# X2C_DC_SHIELD_REVA.net
KiCad netlist of a schematic drawn in EAGLE
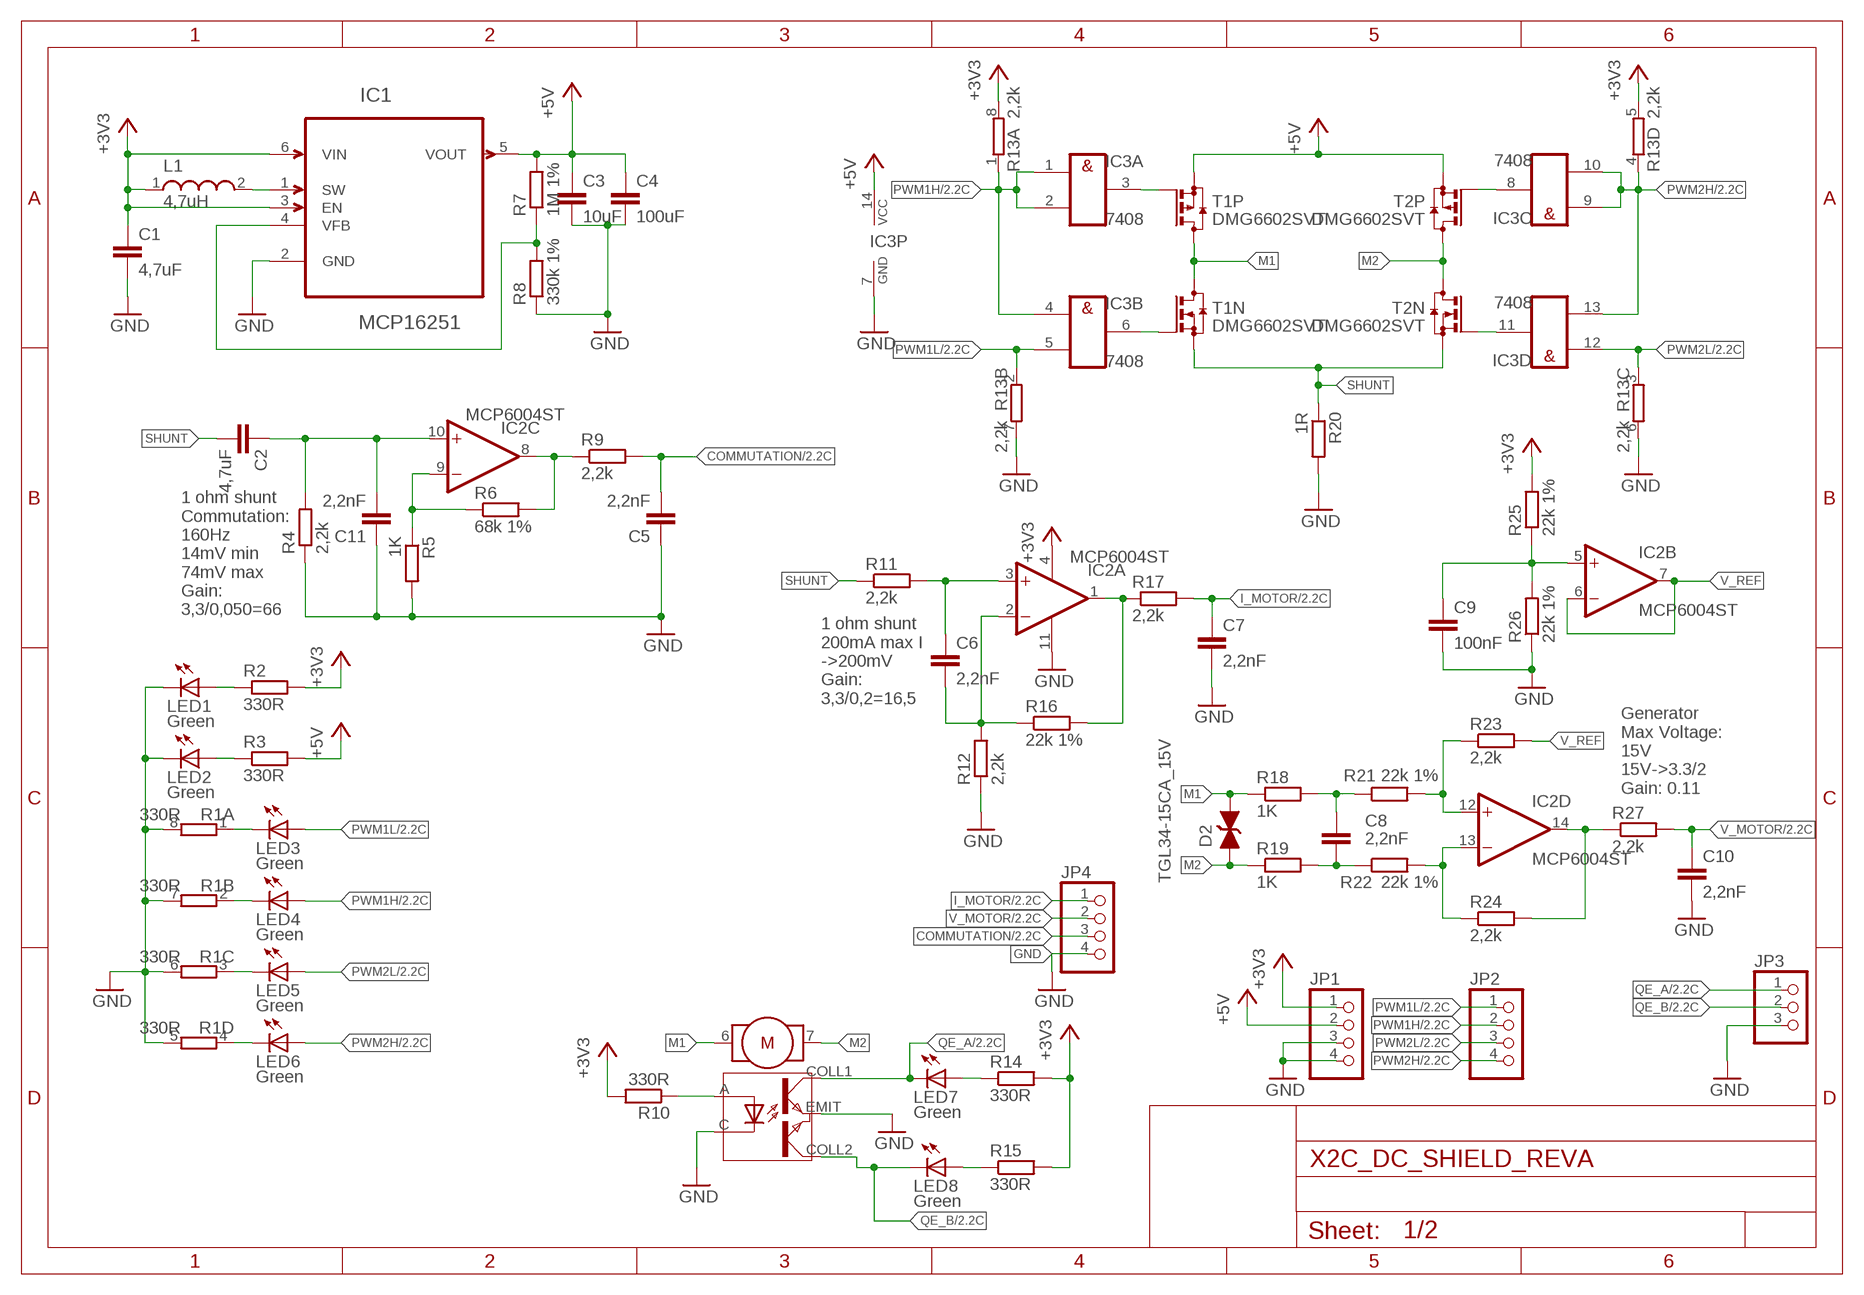
[diagram p0: schematic, sheet 1]
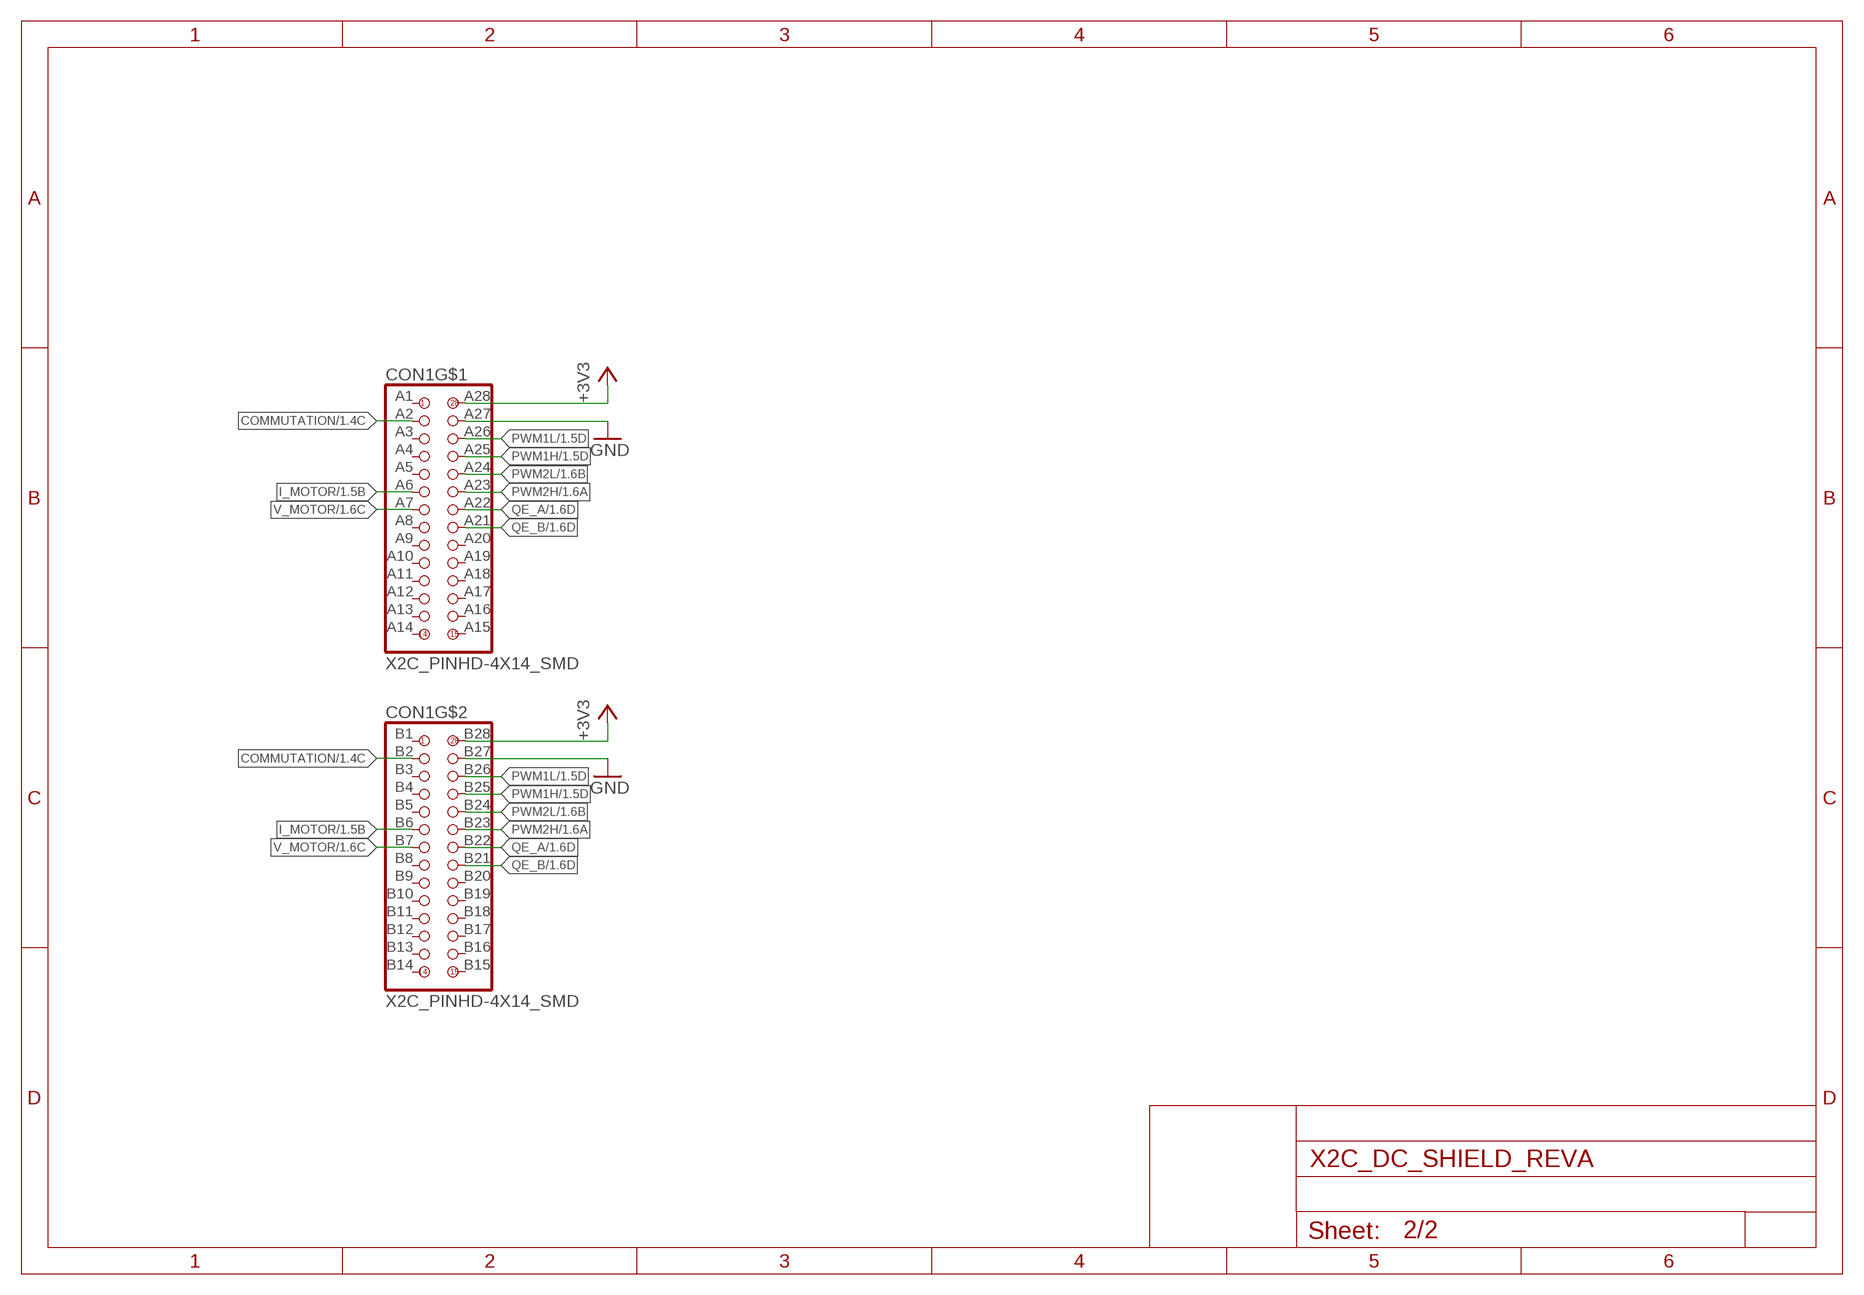
[diagram p1: schematic, sheet 2]

(export (version "E")
  (design (tool "Eeschema 10.0.6"))
  (components
    (comp (ref "C1")
      (value "4,7uF")
      (footprint "eagle-import:C0603K")
      (libsource (lib "eagle-import") (part "C-EU-SMD_0603_4,7UF_16V"))
    )
    (comp (ref "C2")
      (value "4,7uF")
      (footprint "eagle-import:C0603K")
      (libsource (lib "eagle-import") (part "C-EU-SMD_0603_4,7UF_16V"))
    )
    (comp (ref "C3")
      (value "10uF")
      (footprint "eagle-import:C0805K")
      (libsource (lib "eagle-import") (part "C-EU-SMD_0805_10UF_16V"))
    )
    (comp (ref "C4")
      (value "100uF")
      (footprint "eagle-import:C0805K")
      (libsource (lib "eagle-import") (part "C-EU-SMD_0805_100UF_6,3V"))
    )
    (comp (ref "C5")
      (value "2,2nF")
      (footprint "eagle-import:C0603K")
      (libsource (lib "eagle-import") (part "C-EU-SMD_0603_2,2NF"))
    )
    (comp (ref "C6")
      (value "2,2nF")
      (footprint "eagle-import:C0603K")
      (libsource (lib "eagle-import") (part "C-EU-SMD_0603_2,2NF"))
    )
    (comp (ref "C7")
      (value "2,2nF")
      (footprint "eagle-import:C0603K")
      (libsource (lib "eagle-import") (part "C-EU-SMD_0603_2,2NF"))
    )
    (comp (ref "C8")
      (value "2,2nF")
      (footprint "eagle-import:C0603K")
      (libsource (lib "eagle-import") (part "C-EU-SMD_0603_2,2NF"))
    )
    (comp (ref "C9")
      (value "100nF")
      (footprint "eagle-import:C0603K")
      (libsource (lib "eagle-import") (part "C-EU-SMD_0603_100NF_50V"))
    )
    (comp (ref "C10")
      (value "2,2nF")
      (footprint "eagle-import:C0603K")
      (libsource (lib "eagle-import") (part "C-EU-SMD_0603_2,2NF"))
    )
    (comp (ref "C11")
      (value "2,2nF")
      (footprint "eagle-import:C0603K")
      (libsource (lib "eagle-import") (part "C-EU-SMD_0603_2,2NF"))
    )
    (comp (ref "D2")
      (value "TGL34-15CA_15V")
      (footprint "eagle-import:DO213AA")
      (libsource (lib "eagle-import") (part "TRANSIL_DUAL_DIODE"))
    )
    (comp (ref "IC1")
      (value "MCP16251")
      (footprint "eagle-import:SOT95P270X145-6N")
      (libsource (lib "eagle-import") (part "MCP16251"))
    )
    (comp (ref "IC2")
      (value "MCP6004ST")
      (footprint "eagle-import:TSSOP14")
      (libsource (lib "eagle-import") (part "MCP6004ST"))
    )
    (comp (ref "IC3")
      (value "7408")
      (footprint "eagle-import:TSSOP14")
      (libsource (lib "eagle-import") (part "7408"))
    )
    (comp (ref "JP1")
      (value "PINHD-1X4")
      (footprint "eagle-import:1X04")
      (libsource (lib "eagle-import") (part "PINHD-1X4"))
    )
    (comp (ref "JP2")
      (value "PINHD-1X4")
      (footprint "eagle-import:1X04")
      (libsource (lib "eagle-import") (part "PINHD-1X4"))
    )
    (comp (ref "JP3")
      (value "PINHD-1X03_2.54")
      (footprint "eagle-import:1X03")
      (libsource (lib "eagle-import") (part "PINHD-1X03_2.54"))
    )
    (comp (ref "JP4")
      (value "PINHD-1X4")
      (footprint "eagle-import:1X04")
      (libsource (lib "eagle-import") (part "PINHD-1X4"))
    )
    (comp (ref "L1")
      (value "4,7uH")
      (footprint "eagle-import:WE-TPC_3816")
      (libsource (lib "eagle-import") (part "WE-TPC_3816_4,7UH_0,9A"))
    )
    (comp (ref "LED1")
      (value "Green")
      (footprint "eagle-import:CHIPLED_0805")
      (libsource (lib "eagle-import") (part "LEDCHIPLED_0805_GREEN"))
    )
    (comp (ref "LED2")
      (value "Green")
      (footprint "eagle-import:CHIPLED_0805")
      (libsource (lib "eagle-import") (part "LEDCHIPLED_0805_GREEN"))
    )
    (comp (ref "LED3")
      (value "Green")
      (footprint "eagle-import:CHIPLED_0805")
      (libsource (lib "eagle-import") (part "LEDCHIPLED_0805_GREEN"))
    )
    (comp (ref "LED4")
      (value "Green")
      (footprint "eagle-import:CHIPLED_0805")
      (libsource (lib "eagle-import") (part "LEDCHIPLED_0805_GREEN"))
    )
    (comp (ref "LED5")
      (value "Green")
      (footprint "eagle-import:CHIPLED_0805")
      (libsource (lib "eagle-import") (part "LEDCHIPLED_0805_GREEN"))
    )
    (comp (ref "LED6")
      (value "Green")
      (footprint "eagle-import:CHIPLED_0805")
      (libsource (lib "eagle-import") (part "LEDCHIPLED_0805_GREEN"))
    )
    (comp (ref "LED7")
      (value "Green")
      (footprint "eagle-import:CHIPLED_0805")
      (libsource (lib "eagle-import") (part "LEDCHIPLED_0805_GREEN"))
    )
    (comp (ref "LED8")
      (value "Green")
      (footprint "eagle-import:CHIPLED_0805")
      (libsource (lib "eagle-import") (part "LEDCHIPLED_0805_GREEN"))
    )
    (comp (ref "MOT1")
      (value "DC_MOT")
      (footprint "eagle-import:DC_MOTOR")
      (libsource (lib "eagle-import") (part "DC_MOTOR_1"))
    )
    (comp (ref "R1")
      (value "330R")
      (footprint "eagle-import:EXBV8V_A")
      (libsource (lib "eagle-import") (part "4R-N330R"))
    )
    (comp (ref "R2")
      (value "330R")
      (footprint "eagle-import:R0603")
      (libsource (lib "eagle-import") (part "R-EU_SMDR0603_330R"))
    )
    (comp (ref "R3")
      (value "330R")
      (footprint "eagle-import:R0603")
      (libsource (lib "eagle-import") (part "R-EU_SMDR0603_330R"))
    )
    (comp (ref "R4")
      (value "2,2k")
      (footprint "eagle-import:R0603")
      (libsource (lib "eagle-import") (part "R-EU_SMDR0603_2,2K"))
    )
    (comp (ref "R5")
      (value "1K")
      (footprint "eagle-import:R0603")
      (libsource (lib "eagle-import") (part "R-EU_SMDR0603_1K_1%"))
    )
    (comp (ref "R6")
      (value "68k 1%")
      (footprint "eagle-import:R0603")
      (libsource (lib "eagle-import") (part "R-EU_SMDR0603_68K_1%"))
    )
    (comp (ref "R7")
      (value "1M 1%")
      (footprint "eagle-import:R0603")
      (libsource (lib "eagle-import") (part "R-EU_SMDR0603_1M_1%"))
    )
    (comp (ref "R8")
      (value "330k 1%")
      (footprint "eagle-import:R0603")
      (libsource (lib "eagle-import") (part "R-EU_SMDR0603_330K_1%"))
    )
    (comp (ref "R9")
      (value "2,2k")
      (footprint "eagle-import:R0603")
      (libsource (lib "eagle-import") (part "R-EU_SMDR0603_2,2K"))
    )
    (comp (ref "R10")
      (value "330R")
      (footprint "eagle-import:R0603")
      (libsource (lib "eagle-import") (part "R-EU_SMDR0603_330R"))
    )
    (comp (ref "R11")
      (value "2,2k")
      (footprint "eagle-import:R0603")
      (libsource (lib "eagle-import") (part "R-EU_SMDR0603_2,2K"))
    )
    (comp (ref "R12")
      (value "2,2k")
      (footprint "eagle-import:R0603")
      (libsource (lib "eagle-import") (part "R-EU_SMDR0603_2,2K"))
    )
    (comp (ref "R13")
      (value "2,2k")
      (footprint "eagle-import:EXBV8V_A")
      (libsource (lib "eagle-import") (part "4R-N2,2K"))
    )
    (comp (ref "R14")
      (value "330R")
      (footprint "eagle-import:R0603")
      (libsource (lib "eagle-import") (part "R-EU_SMDR0603_330R"))
    )
    (comp (ref "R15")
      (value "330R")
      (footprint "eagle-import:R0603")
      (libsource (lib "eagle-import") (part "R-EU_SMDR0603_330R"))
    )
    (comp (ref "R16")
      (value "22k 1%")
      (footprint "eagle-import:R0603")
      (libsource (lib "eagle-import") (part "R-EU_SMDR0603_22K_1%"))
    )
    (comp (ref "R17")
      (value "2,2k")
      (footprint "eagle-import:R0603")
      (libsource (lib "eagle-import") (part "R-EU_SMDR0603_2,2K"))
    )
    (comp (ref "R18")
      (value "1K")
      (footprint "eagle-import:R0603")
      (libsource (lib "eagle-import") (part "R-EU_SMDR0603_1K_1%"))
    )
    (comp (ref "R19")
      (value "1K")
      (footprint "eagle-import:R0603")
      (libsource (lib "eagle-import") (part "R-EU_SMDR0603_1K_1%"))
    )
    (comp (ref "R20")
      (value "1R")
      (footprint "eagle-import:R0805")
      (libsource (lib "eagle-import") (part "R-EU_SMDR0805_1R_1%"))
    )
    (comp (ref "R21")
      (value "22k 1%")
      (footprint "eagle-import:R0603")
      (libsource (lib "eagle-import") (part "R-EU_SMDR0603_22K_1%"))
    )
    (comp (ref "R22")
      (value "22k 1%")
      (footprint "eagle-import:R0603")
      (libsource (lib "eagle-import") (part "R-EU_SMDR0603_22K_1%"))
    )
    (comp (ref "R23")
      (value "2,2k")
      (footprint "eagle-import:R0603")
      (libsource (lib "eagle-import") (part "R-EU_SMDR0603_2,2K"))
    )
    (comp (ref "R24")
      (value "2,2k")
      (footprint "eagle-import:R0603")
      (libsource (lib "eagle-import") (part "R-EU_SMDR0603_2,2K"))
    )
    (comp (ref "R25")
      (value "22k 1%")
      (footprint "eagle-import:R0603")
      (libsource (lib "eagle-import") (part "R-EU_SMDR0603_22K_1%"))
    )
    (comp (ref "R26")
      (value "22k 1%")
      (footprint "eagle-import:R0603")
      (libsource (lib "eagle-import") (part "R-EU_SMDR0603_22K_1%"))
    )
    (comp (ref "R27")
      (value "2,2k")
      (footprint "eagle-import:R0603")
      (libsource (lib "eagle-import") (part "R-EU_SMDR0603_2,2K"))
    )
    (comp (ref "T1")
      (value "DMG6602SVT")
      (footprint "eagle-import:TSOT23-6")
      (libsource (lib "eagle-import") (part "DMG6602SVT"))
    )
    (comp (ref "T2")
      (value "DMG6602SVT")
      (footprint "eagle-import:TSOT23-6")
      (libsource (lib "eagle-import") (part "DMG6602SVT"))
    )
    (comp (ref "CON1")
      (value "X2C_PINHD-4X14_SMD")
      (footprint "eagle-import:X2C_4X14_SMD")
      (libsource (lib "eagle-import") (part "X2C_PINHD-4X14_SMD"))
    )
  )
  (nets
    (net (code "1") (name "+3V3") (class "Default")
      (node (ref "C1") (pin "1") (pinfunction "1_1") (pintype "passive"))
      (node (ref "CON1") (pin "A28") (pinfunction "A28_A28") (pintype "passive"))
      (node (ref "CON1") (pin "B28") (pinfunction "A28_B28") (pintype "passive"))
      (node (ref "IC1") (pin "3") (pinfunction "EN_3") (pintype "input"))
      (node (ref "IC1") (pin "6") (pinfunction "VIN_6") (pintype "input"))
      (node (ref "IC2") (pin "4") (pinfunction "V+_4") (pintype "power_in"))
      (node (ref "JP1") (pin "1") (pinfunction "1_1") (pintype "passive"))
      (node (ref "L1") (pin "1") (pinfunction "1_1") (pintype "passive"))
      (node (ref "R10") (pin "2") (pinfunction "2_2") (pintype "passive"))
      (node (ref "R13") (pin "5") (pinfunction "2_5") (pintype "passive"))
      (node (ref "R13") (pin "8") (pinfunction "2_8") (pintype "passive"))
      (node (ref "R14") (pin "2") (pinfunction "2_2") (pintype "passive"))
      (node (ref "R15") (pin "2") (pinfunction "2_2") (pintype "passive"))
      (node (ref "R2") (pin "2") (pinfunction "2_2") (pintype "passive"))
      (node (ref "R25") (pin "2") (pinfunction "2_2") (pintype "passive"))
    )
    (net (code "2") (name "+5V") (class "Default")
      (node (ref "C3") (pin "1") (pinfunction "1_1") (pintype "passive"))
      (node (ref "C4") (pin "1") (pinfunction "1_1") (pintype "passive"))
      (node (ref "IC1") (pin "5") (pinfunction "VOUT_5") (pintype "output"))
      (node (ref "IC3") (pin "14") (pinfunction "VCC_14") (pintype "power_in"))
      (node (ref "JP1") (pin "2") (pinfunction "2_2") (pintype "passive"))
      (node (ref "R3") (pin "2") (pinfunction "2_2") (pintype "passive"))
      (node (ref "R7") (pin "2") (pinfunction "2_2") (pintype "passive"))
      (node (ref "T1") (pin "2") (pinfunction "S_2") (pintype "passive"))
      (node (ref "T2") (pin "2") (pinfunction "S_2") (pintype "passive"))
    )
    (net (code "3") (name "COMMUTATION") (class "Default")
      (node (ref "C5") (pin "2") (pinfunction "2_2") (pintype "passive"))
      (node (ref "CON1") (pin "A2") (pinfunction "A2_A2") (pintype "passive"))
      (node (ref "CON1") (pin "B2") (pinfunction "A2_B2") (pintype "passive"))
      (node (ref "JP4") (pin "3") (pinfunction "3_3") (pintype "passive"))
      (node (ref "R9") (pin "2") (pinfunction "2_2") (pintype "passive"))
    )
    (net (code "4") (name "GND") (class "Default")
      (node (ref "C1") (pin "2") (pinfunction "2_2") (pintype "passive"))
      (node (ref "C10") (pin "2") (pinfunction "2_2") (pintype "passive"))
      (node (ref "C11") (pin "1") (pinfunction "1_1") (pintype "passive"))
      (node (ref "C3") (pin "2") (pinfunction "2_2") (pintype "passive"))
      (node (ref "C4") (pin "2") (pinfunction "2_2") (pintype "passive"))
      (node (ref "C5") (pin "1") (pinfunction "1_1") (pintype "passive"))
      (node (ref "C7") (pin "2") (pinfunction "2_2") (pintype "passive"))
      (node (ref "C9") (pin "2") (pinfunction "2_2") (pintype "passive"))
      (node (ref "CON1") (pin "A27") (pinfunction "A27_A27") (pintype "passive"))
      (node (ref "CON1") (pin "B27") (pinfunction "A27_B27") (pintype "passive"))
      (node (ref "IC1") (pin "2") (pinfunction "GND_2") (pintype "passive"))
      (node (ref "IC2") (pin "11") (pinfunction "V-_11") (pintype "power_in"))
      (node (ref "IC3") (pin "7") (pinfunction "GND_7") (pintype "power_in"))
      (node (ref "JP1") (pin "3") (pinfunction "3_3") (pintype "passive"))
      (node (ref "JP1") (pin "4") (pinfunction "4_4") (pintype "passive"))
      (node (ref "JP3") (pin "3") (pinfunction "3_3") (pintype "passive"))
      (node (ref "JP4") (pin "4") (pinfunction "4_4") (pintype "passive"))
      (node (ref "LED1") (pin "C") (pinfunction "C_C") (pintype "passive"))
      (node (ref "LED2") (pin "C") (pinfunction "C_C") (pintype "passive"))
      (node (ref "MOT1") (pin "C") (pinfunction "C_C") (pintype "passive"))
      (node (ref "MOT1") (pin "EMIT") (pinfunction "EMIT_EMIT") (pintype "passive"))
      (node (ref "R1") (pin "5") (pinfunction "2_5") (pintype "passive"))
      (node (ref "R1") (pin "6") (pinfunction "2_6") (pintype "passive"))
      (node (ref "R1") (pin "7") (pinfunction "2_7") (pintype "passive"))
      (node (ref "R1") (pin "8") (pinfunction "2_8") (pintype "passive"))
      (node (ref "R12") (pin "1") (pinfunction "1_1") (pintype "passive"))
      (node (ref "R13") (pin "6") (pinfunction "2_6") (pintype "passive"))
      (node (ref "R13") (pin "7") (pinfunction "2_7") (pintype "passive"))
      (node (ref "R20") (pin "2") (pinfunction "2_2") (pintype "passive"))
      (node (ref "R26") (pin "1") (pinfunction "1_1") (pintype "passive"))
      (node (ref "R4") (pin "1") (pinfunction "1_1") (pintype "passive"))
      (node (ref "R5") (pin "2") (pinfunction "2_2") (pintype "passive"))
      (node (ref "R8") (pin "1") (pinfunction "1_1") (pintype "passive"))
    )
    (net (code "5") (name "I_MOTOR") (class "Default")
      (node (ref "C7") (pin "1") (pinfunction "1_1") (pintype "passive"))
      (node (ref "CON1") (pin "A6") (pinfunction "A6_A6") (pintype "passive"))
      (node (ref "CON1") (pin "B6") (pinfunction "A6_B6") (pintype "passive"))
      (node (ref "JP4") (pin "1") (pinfunction "1_1") (pintype "passive"))
      (node (ref "R17") (pin "2") (pinfunction "2_2") (pintype "passive"))
    )
    (net (code "6") (name "M1") (class "Default")
      (node (ref "D2") (pin "C") (pinfunction "P$2_C") (pintype "bidirectional"))
      (node (ref "MOT1") (pin "6") (pinfunction "MOT1_6") (pintype "passive"))
      (node (ref "R18") (pin "1") (pinfunction "1_1") (pintype "passive"))
      (node (ref "T1") (pin "4") (pinfunction "D_4") (pintype "passive"))
      (node (ref "T1") (pin "6") (pinfunction "D_6") (pintype "passive"))
    )
    (net (code "7") (name "M2") (class "Default")
      (node (ref "D2") (pin "A") (pinfunction "P$1_A") (pintype "bidirectional"))
      (node (ref "MOT1") (pin "7") (pinfunction "MOT2_7") (pintype "passive"))
      (node (ref "R19") (pin "1") (pinfunction "1_1") (pintype "passive"))
      (node (ref "T2") (pin "4") (pinfunction "D_4") (pintype "passive"))
      (node (ref "T2") (pin "6") (pinfunction "D_6") (pintype "passive"))
    )
    (net (code "8") (name "Net-(C8-Pad1)") (class "Default")
      (node (ref "C8") (pin "1") (pinfunction "1_1") (pintype "passive"))
      (node (ref "R18") (pin "2") (pinfunction "2_2") (pintype "passive"))
      (node (ref "R21") (pin "1") (pinfunction "1_1") (pintype "passive"))
    )
    (net (code "9") (name "Net-(C8-Pad2)") (class "Default")
      (node (ref "C8") (pin "2") (pinfunction "2_2") (pintype "passive"))
      (node (ref "R19") (pin "2") (pinfunction "2_2") (pintype "passive"))
      (node (ref "R22") (pin "1") (pinfunction "1_1") (pintype "passive"))
    )
    (net (code "10") (name "Net-(IC1-SW)") (class "Default")
      (node (ref "IC1") (pin "1") (pinfunction "SW_1") (pintype "input"))
      (node (ref "L1") (pin "2") (pinfunction "2_2") (pintype "passive"))
    )
    (net (code "11") (name "Net-(IC1-VFB)") (class "Default")
      (node (ref "IC1") (pin "4") (pinfunction "VFB_4") (pintype "input"))
      (node (ref "R7") (pin "1") (pinfunction "1_1") (pintype "passive"))
      (node (ref "R8") (pin "2") (pinfunction "2_2") (pintype "passive"))
    )
    (net (code "12") (name "Net-(IC2A-+IN)") (class "Default")
      (node (ref "C6") (pin "1") (pinfunction "1_1") (pintype "passive"))
      (node (ref "IC2") (pin "3") (pinfunction "+IN_3") (pintype "input"))
      (node (ref "R11") (pin "2") (pinfunction "2_2") (pintype "passive"))
    )
    (net (code "13") (name "Net-(IC2A--IN)") (class "Default")
      (node (ref "C6") (pin "2") (pinfunction "2_2") (pintype "passive"))
      (node (ref "IC2") (pin "2") (pinfunction "-IN_2") (pintype "input"))
      (node (ref "R12") (pin "2") (pinfunction "2_2") (pintype "passive"))
      (node (ref "R16") (pin "1") (pinfunction "1_1") (pintype "passive"))
    )
    (net (code "14") (name "Net-(IC2A-OUT)") (class "Default")
      (node (ref "IC2") (pin "1") (pinfunction "OUT_1") (pintype "output"))
      (node (ref "R16") (pin "2") (pinfunction "2_2") (pintype "passive"))
      (node (ref "R17") (pin "1") (pinfunction "1_1") (pintype "passive"))
    )
    (net (code "15") (name "Net-(IC2B-+IN)") (class "Default")
      (node (ref "C9") (pin "1") (pinfunction "1_1") (pintype "passive"))
      (node (ref "IC2") (pin "5") (pinfunction "+IN_5") (pintype "input"))
      (node (ref "R25") (pin "1") (pinfunction "1_1") (pintype "passive"))
      (node (ref "R26") (pin "2") (pinfunction "2_2") (pintype "passive"))
    )
    (net (code "16") (name "Net-(IC2C-+IN)") (class "Default")
      (node (ref "C11") (pin "2") (pinfunction "2_2") (pintype "passive"))
      (node (ref "C2") (pin "1") (pinfunction "1_1") (pintype "passive"))
      (node (ref "IC2") (pin "10") (pinfunction "+IN_10") (pintype "input"))
      (node (ref "R4") (pin "2") (pinfunction "2_2") (pintype "passive"))
    )
    (net (code "17") (name "Net-(IC2C--IN)") (class "Default")
      (node (ref "IC2") (pin "9") (pinfunction "-IN_9") (pintype "input"))
      (node (ref "R5") (pin "1") (pinfunction "1_1") (pintype "passive"))
      (node (ref "R6") (pin "1") (pinfunction "1_1") (pintype "passive"))
    )
    (net (code "18") (name "Net-(IC2C-OUT)") (class "Default")
      (node (ref "IC2") (pin "8") (pinfunction "OUT_8") (pintype "output"))
      (node (ref "R6") (pin "2") (pinfunction "2_2") (pintype "passive"))
      (node (ref "R9") (pin "1") (pinfunction "1_1") (pintype "passive"))
    )
    (net (code "19") (name "Net-(IC2D-+IN)") (class "Default")
      (node (ref "IC2") (pin "12") (pinfunction "+IN_12") (pintype "input"))
      (node (ref "R21") (pin "2") (pinfunction "2_2") (pintype "passive"))
      (node (ref "R23") (pin "1") (pinfunction "1_1") (pintype "passive"))
    )
    (net (code "20") (name "Net-(IC2D--IN)") (class "Default")
      (node (ref "IC2") (pin "13") (pinfunction "-IN_13") (pintype "input"))
      (node (ref "R22") (pin "2") (pinfunction "2_2") (pintype "passive"))
      (node (ref "R24") (pin "1") (pinfunction "1_1") (pintype "passive"))
    )
    (net (code "21") (name "Net-(IC2D-OUT)") (class "Default")
      (node (ref "IC2") (pin "14") (pinfunction "OUT_14") (pintype "output"))
      (node (ref "R24") (pin "2") (pinfunction "2_2") (pintype "passive"))
      (node (ref "R27") (pin "1") (pinfunction "1_1") (pintype "passive"))
    )
    (net (code "22") (name "Net-(IC3A-O)") (class "Default")
      (node (ref "IC3") (pin "3") (pinfunction "O_3") (pintype "output"))
      (node (ref "T1") (pin "3") (pinfunction "G_3") (pintype "passive"))
    )
    (net (code "23") (name "Net-(IC3B-O)") (class "Default")
      (node (ref "IC3") (pin "6") (pinfunction "O_6") (pintype "output"))
      (node (ref "T1") (pin "1") (pinfunction "G_1") (pintype "passive"))
    )
    (net (code "24") (name "Net-(IC3C-O)") (class "Default")
      (node (ref "IC3") (pin "8") (pinfunction "O_8") (pintype "output"))
      (node (ref "T2") (pin "3") (pinfunction "G_3") (pintype "passive"))
    )
    (net (code "25") (name "Net-(IC3D-O)") (class "Default")
      (node (ref "IC3") (pin "11") (pinfunction "O_11") (pintype "output"))
      (node (ref "T2") (pin "1") (pinfunction "G_1") (pintype "passive"))
    )
    (net (code "26") (name "Net-(LED1-PadA)") (class "Default")
      (node (ref "LED1") (pin "A") (pinfunction "A_A") (pintype "passive"))
      (node (ref "R2") (pin "1") (pinfunction "1_1") (pintype "passive"))
    )
    (net (code "27") (name "Net-(LED2-PadA)") (class "Default")
      (node (ref "LED2") (pin "A") (pinfunction "A_A") (pintype "passive"))
      (node (ref "R3") (pin "1") (pinfunction "1_1") (pintype "passive"))
    )
    (net (code "28") (name "Net-(LED3-PadC)") (class "Default")
      (node (ref "LED3") (pin "C") (pinfunction "C_C") (pintype "passive"))
      (node (ref "R1") (pin "1") (pinfunction "1_1") (pintype "passive"))
    )
    (net (code "29") (name "Net-(LED7-PadA)") (class "Default")
      (node (ref "LED7") (pin "A") (pinfunction "A_A") (pintype "passive"))
      (node (ref "R14") (pin "1") (pinfunction "1_1") (pintype "passive"))
    )
    (net (code "30") (name "Net-(LED8-PadA)") (class "Default")
      (node (ref "LED8") (pin "A") (pinfunction "A_A") (pintype "passive"))
      (node (ref "R15") (pin "1") (pinfunction "1_1") (pintype "passive"))
    )
    (net (code "31") (name "Net-(MOT1-PadA)") (class "Default")
      (node (ref "MOT1") (pin "A") (pinfunction "A_A") (pintype "passive"))
      (node (ref "R10") (pin "1") (pinfunction "1_1") (pintype "passive"))
    )
    (net (code "32") (name "Net-(R1B-1)") (class "Default")
      (node (ref "LED4") (pin "C") (pinfunction "C_C") (pintype "passive"))
      (node (ref "R1") (pin "2") (pinfunction "1_2") (pintype "passive"))
    )
    (net (code "33") (name "Net-(R1C-1)") (class "Default")
      (node (ref "LED5") (pin "C") (pinfunction "C_C") (pintype "passive"))
      (node (ref "R1") (pin "3") (pinfunction "1_3") (pintype "passive"))
    )
    (net (code "34") (name "Net-(R1D-1)") (class "Default")
      (node (ref "LED6") (pin "C") (pinfunction "C_C") (pintype "passive"))
      (node (ref "R1") (pin "4") (pinfunction "1_4") (pintype "passive"))
    )
    (net (code "35") (name "PWM1H") (class "Default")
      (node (ref "CON1") (pin "A25") (pinfunction "A25_A25") (pintype "passive"))
      (node (ref "CON1") (pin "B25") (pinfunction "A25_B25") (pintype "passive"))
      (node (ref "IC3") (pin "1") (pinfunction "I0_1") (pintype "input"))
      (node (ref "IC3") (pin "2") (pinfunction "I1_2") (pintype "input"))
      (node (ref "IC3") (pin "4") (pinfunction "I0_4") (pintype "input"))
      (node (ref "JP2") (pin "2") (pinfunction "2_2") (pintype "passive"))
      (node (ref "LED4") (pin "A") (pinfunction "A_A") (pintype "passive"))
      (node (ref "R13") (pin "1") (pinfunction "1_1") (pintype "passive"))
    )
    (net (code "36") (name "PWM1L") (class "Default")
      (node (ref "CON1") (pin "A26") (pinfunction "A26_A26") (pintype "passive"))
      (node (ref "CON1") (pin "B26") (pinfunction "A26_B26") (pintype "passive"))
      (node (ref "IC3") (pin "5") (pinfunction "I1_5") (pintype "input"))
      (node (ref "JP2") (pin "1") (pinfunction "1_1") (pintype "passive"))
      (node (ref "LED3") (pin "A") (pinfunction "A_A") (pintype "passive"))
      (node (ref "R13") (pin "2") (pinfunction "1_2") (pintype "passive"))
    )
    (net (code "37") (name "PWM2H") (class "Default")
      (node (ref "CON1") (pin "A23") (pinfunction "A23_A23") (pintype "passive"))
      (node (ref "CON1") (pin "B23") (pinfunction "A23_B23") (pintype "passive"))
      (node (ref "IC3") (pin "10") (pinfunction "I1_10") (pintype "input"))
      (node (ref "IC3") (pin "13") (pinfunction "I1_13") (pintype "input"))
      (node (ref "IC3") (pin "9") (pinfunction "I0_9") (pintype "input"))
      (node (ref "JP2") (pin "4") (pinfunction "4_4") (pintype "passive"))
      (node (ref "LED6") (pin "A") (pinfunction "A_A") (pintype "passive"))
      (node (ref "R13") (pin "4") (pinfunction "1_4") (pintype "passive"))
    )
    (net (code "38") (name "PWM2L") (class "Default")
      (node (ref "CON1") (pin "A24") (pinfunction "A24_A24") (pintype "passive"))
      (node (ref "CON1") (pin "B24") (pinfunction "A24_B24") (pintype "passive"))
      (node (ref "IC3") (pin "12") (pinfunction "I0_12") (pintype "input"))
      (node (ref "JP2") (pin "3") (pinfunction "3_3") (pintype "passive"))
      (node (ref "LED5") (pin "A") (pinfunction "A_A") (pintype "passive"))
      (node (ref "R13") (pin "3") (pinfunction "1_3") (pintype "passive"))
    )
    (net (code "39") (name "QE_A") (class "Default")
      (node (ref "CON1") (pin "A22") (pinfunction "A22_A22") (pintype "passive"))
      (node (ref "CON1") (pin "B22") (pinfunction "A22_B22") (pintype "passive"))
      (node (ref "JP3") (pin "1") (pinfunction "1_1") (pintype "passive"))
      (node (ref "LED7") (pin "C") (pinfunction "C_C") (pintype "passive"))
      (node (ref "MOT1") (pin "COLL1") (pinfunction "COL1_COLL1") (pintype "passive"))
    )
    (net (code "40") (name "QE_B") (class "Default")
      (node (ref "CON1") (pin "A21") (pinfunction "A21_A21") (pintype "passive"))
      (node (ref "CON1") (pin "B21") (pinfunction "A21_B21") (pintype "passive"))
      (node (ref "JP3") (pin "2") (pinfunction "2_2") (pintype "passive"))
      (node (ref "LED8") (pin "C") (pinfunction "C_C") (pintype "passive"))
      (node (ref "MOT1") (pin "COLL2") (pinfunction "COL2_COLL2") (pintype "passive"))
    )
    (net (code "41") (name "SHUNT") (class "Default")
      (node (ref "C2") (pin "2") (pinfunction "2_2") (pintype "passive"))
      (node (ref "R11") (pin "1") (pinfunction "1_1") (pintype "passive"))
      (node (ref "R20") (pin "1") (pinfunction "1_1") (pintype "passive"))
      (node (ref "T1") (pin "5") (pinfunction "S_5") (pintype "passive"))
      (node (ref "T2") (pin "5") (pinfunction "S_5") (pintype "passive"))
    )
    (net (code "42") (name "V_MOTOR") (class "Default")
      (node (ref "C10") (pin "1") (pinfunction "1_1") (pintype "passive"))
      (node (ref "CON1") (pin "A7") (pinfunction "A7_A7") (pintype "passive"))
      (node (ref "CON1") (pin "B7") (pinfunction "A7_B7") (pintype "passive"))
      (node (ref "JP4") (pin "2") (pinfunction "2_2") (pintype "passive"))
      (node (ref "R27") (pin "2") (pinfunction "2_2") (pintype "passive"))
    )
    (net (code "43") (name "V_REF") (class "Default")
      (node (ref "IC2") (pin "6") (pinfunction "-IN_6") (pintype "input"))
      (node (ref "IC2") (pin "7") (pinfunction "OUT_7") (pintype "output"))
      (node (ref "R23") (pin "2") (pinfunction "2_2") (pintype "passive"))
    )
    (net (code "44") (name "unconnected-(CON1-PadA1)") (class "Default")
      (node (ref "CON1") (pin "A1") (pinfunction "A1_A1") (pintype "passive"))
    )
    (net (code "45") (name "unconnected-(CON1-PadA3)") (class "Default")
      (node (ref "CON1") (pin "A3") (pinfunction "A3_A3") (pintype "passive"))
    )
    (net (code "46") (name "unconnected-(CON1-PadA4)") (class "Default")
      (node (ref "CON1") (pin "A4") (pinfunction "A4_A4") (pintype "passive"))
    )
    (net (code "47") (name "unconnected-(CON1-PadA5)") (class "Default")
      (node (ref "CON1") (pin "A5") (pinfunction "A5_A5") (pintype "passive"))
    )
    (net (code "48") (name "unconnected-(CON1-PadA8)") (class "Default")
      (node (ref "CON1") (pin "A8") (pinfunction "A8_A8") (pintype "passive"))
    )
    (net (code "49") (name "unconnected-(CON1-PadA9)") (class "Default")
      (node (ref "CON1") (pin "A9") (pinfunction "A9_A9") (pintype "passive"))
    )
    (net (code "50") (name "unconnected-(CON1-PadA10)") (class "Default")
      (node (ref "CON1") (pin "A10") (pinfunction "A10_A10") (pintype "passive"))
    )
    (net (code "51") (name "unconnected-(CON1-PadA11)") (class "Default")
      (node (ref "CON1") (pin "A11") (pinfunction "A11_A11") (pintype "passive"))
    )
    (net (code "52") (name "unconnected-(CON1-PadA12)") (class "Default")
      (node (ref "CON1") (pin "A12") (pinfunction "A12_A12") (pintype "passive"))
    )
    (net (code "53") (name "unconnected-(CON1-PadA13)") (class "Default")
      (node (ref "CON1") (pin "A13") (pinfunction "A13_A13") (pintype "passive"))
    )
    (net (code "54") (name "unconnected-(CON1-PadA14)") (class "Default")
      (node (ref "CON1") (pin "A14") (pinfunction "A14_A14") (pintype "passive"))
    )
    (net (code "55") (name "unconnected-(CON1-PadA15)") (class "Default")
      (node (ref "CON1") (pin "A15") (pinfunction "A15_A15") (pintype "passive"))
    )
    (net (code "56") (name "unconnected-(CON1-PadA16)") (class "Default")
      (node (ref "CON1") (pin "A16") (pinfunction "A16_A16") (pintype "passive"))
    )
    (net (code "57") (name "unconnected-(CON1-PadA17)") (class "Default")
      (node (ref "CON1") (pin "A17") (pinfunction "A17_A17") (pintype "passive"))
    )
    (net (code "58") (name "unconnected-(CON1-PadA18)") (class "Default")
      (node (ref "CON1") (pin "A18") (pinfunction "A18_A18") (pintype "passive"))
    )
    (net (code "59") (name "unconnected-(CON1-PadA19)") (class "Default")
      (node (ref "CON1") (pin "A19") (pinfunction "A19_A19") (pintype "passive"))
    )
    (net (code "60") (name "unconnected-(CON1-PadA20)") (class "Default")
      (node (ref "CON1") (pin "A20") (pinfunction "A20_A20") (pintype "passive"))
    )
    (net (code "61") (name "unconnected-(CON1B-A1-PadB1)") (class "Default")
      (node (ref "CON1") (pin "B1") (pinfunction "A1_B1") (pintype "passive"))
    )
    (net (code "62") (name "unconnected-(CON1B-A3-PadB3)") (class "Default")
      (node (ref "CON1") (pin "B3") (pinfunction "A3_B3") (pintype "passive"))
    )
    (net (code "63") (name "unconnected-(CON1B-A4-PadB4)") (class "Default")
      (node (ref "CON1") (pin "B4") (pinfunction "A4_B4") (pintype "passive"))
    )
    (net (code "64") (name "unconnected-(CON1B-A5-PadB5)") (class "Default")
      (node (ref "CON1") (pin "B5") (pinfunction "A5_B5") (pintype "passive"))
    )
    (net (code "65") (name "unconnected-(CON1B-A8-PadB8)") (class "Default")
      (node (ref "CON1") (pin "B8") (pinfunction "A8_B8") (pintype "passive"))
    )
    (net (code "66") (name "unconnected-(CON1B-A9-PadB9)") (class "Default")
      (node (ref "CON1") (pin "B9") (pinfunction "A9_B9") (pintype "passive"))
    )
    (net (code "67") (name "unconnected-(CON1B-A10-PadB10)") (class "Default")
      (node (ref "CON1") (pin "B10") (pinfunction "A10_B10") (pintype "passive"))
    )
    (net (code "68") (name "unconnected-(CON1B-A11-PadB11)") (class "Default")
      (node (ref "CON1") (pin "B11") (pinfunction "A11_B11") (pintype "passive"))
    )
    (net (code "69") (name "unconnected-(CON1B-A12-PadB12)") (class "Default")
      (node (ref "CON1") (pin "B12") (pinfunction "A12_B12") (pintype "passive"))
    )
    (net (code "70") (name "unconnected-(CON1B-A13-PadB13)") (class "Default")
      (node (ref "CON1") (pin "B13") (pinfunction "A13_B13") (pintype "passive"))
    )
    (net (code "71") (name "unconnected-(CON1B-A14-PadB14)") (class "Default")
      (node (ref "CON1") (pin "B14") (pinfunction "A14_B14") (pintype "passive"))
    )
    (net (code "72") (name "unconnected-(CON1B-A15-PadB15)") (class "Default")
      (node (ref "CON1") (pin "B15") (pinfunction "A15_B15") (pintype "passive"))
    )
    (net (code "73") (name "unconnected-(CON1B-A16-PadB16)") (class "Default")
      (node (ref "CON1") (pin "B16") (pinfunction "A16_B16") (pintype "passive"))
    )
    (net (code "74") (name "unconnected-(CON1B-A17-PadB17)") (class "Default")
      (node (ref "CON1") (pin "B17") (pinfunction "A17_B17") (pintype "passive"))
    )
    (net (code "75") (name "unconnected-(CON1B-A18-PadB18)") (class "Default")
      (node (ref "CON1") (pin "B18") (pinfunction "A18_B18") (pintype "passive"))
    )
    (net (code "76") (name "unconnected-(CON1B-A19-PadB19)") (class "Default")
      (node (ref "CON1") (pin "B19") (pinfunction "A19_B19") (pintype "passive"))
    )
    (net (code "77") (name "unconnected-(CON1B-A20-PadB20)") (class "Default")
      (node (ref "CON1") (pin "B20") (pinfunction "A20_B20") (pintype "passive"))
    )
  )
)
